# Connectors.net
KiCad netlist of a schematic drawn in Altium Designer
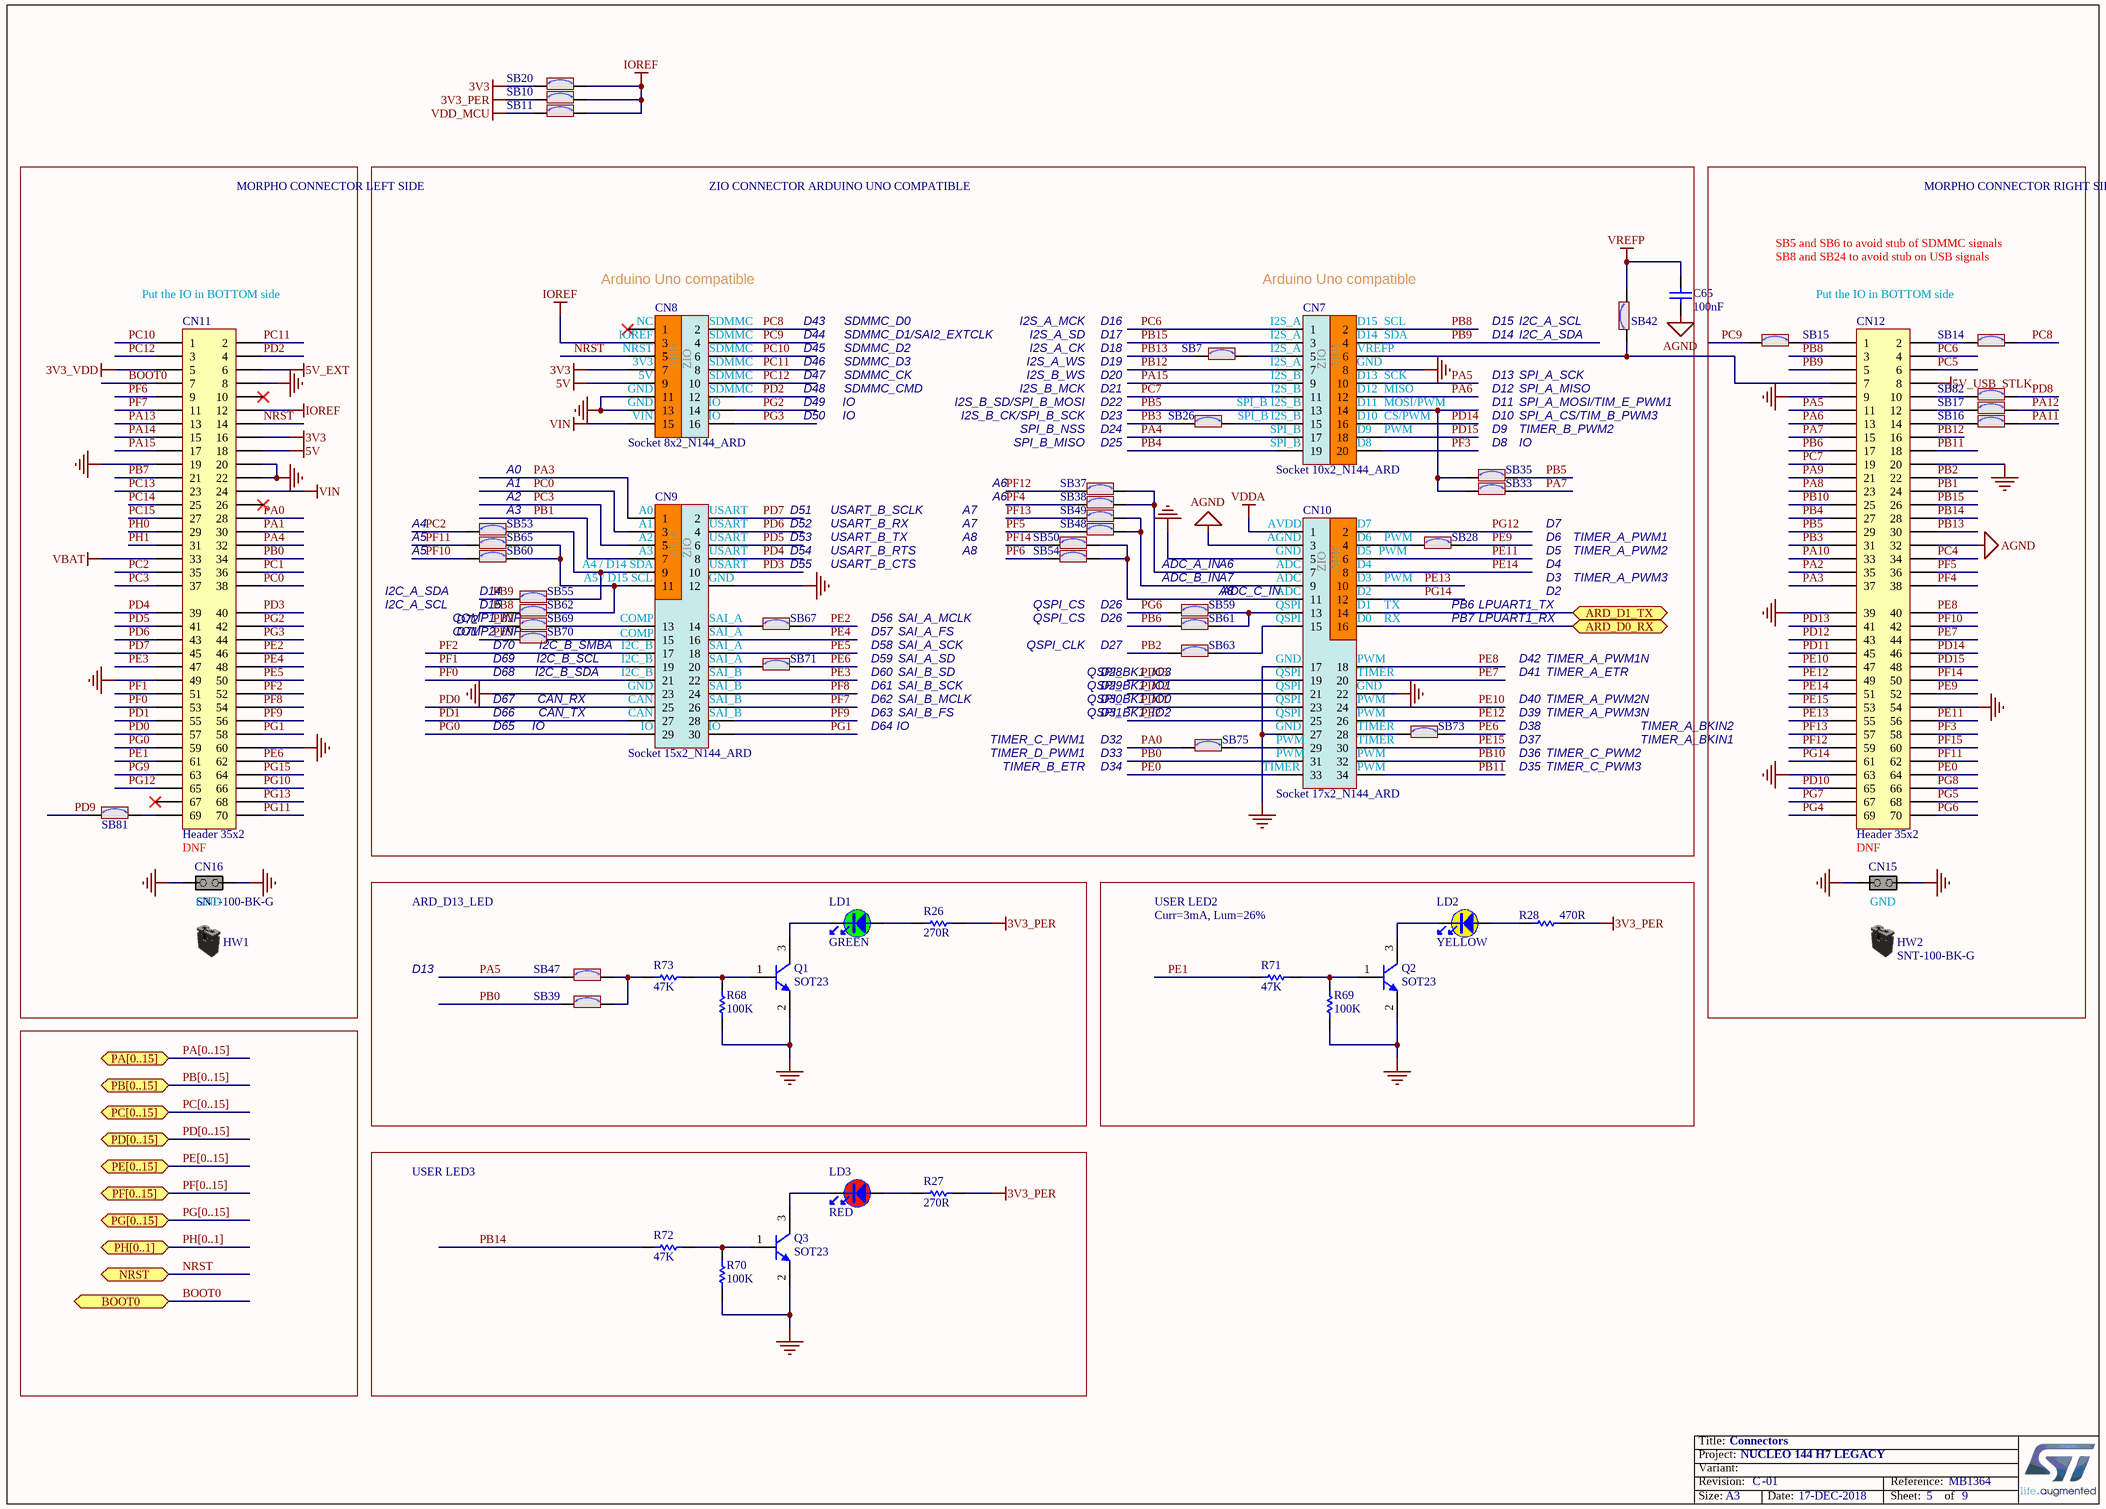
[diagram p0: Connectors.SchDoc]

(export (version "E")
  (design (tool "Eeschema 10.0.6"))
  (components
    (comp (ref "C65")
      (value "100nF")
      (footprint "C0603")
      (description "Capacitor, MLCC, 100nF, 6V3, X5R, 10%, 0603, T=0,8mm")
      (fields
        (field (name "INTERNAL_PART_NUMBER") "MCD-00237")
        (field (name "MANUFACTURER_PART_NUMBER") "CC0603KRX5R5BB104")
        (field (name "PROVIDED_BY") "SUBCO")
      )
      (libsource (lib "MCD_PARTS_database") (part "Capacitor"))
    )
    (comp (ref "CN7")
      (value "Socket 10x2_N144_ARD")
      (footprint "CON_SAMTEC_SSW-110-23-X-D_N144_ARD")
      (description "Socket, 10x2, 2.54mm, VR, TH, Height 8.51mm/10mm, Low insertion force.")
      (fields
        (field (name "INTERNAL_PART_NUMBER") "MCD-01039")
        (field (name "MANUFACTURER_PART_NUMBER") "SSW-110-23-x-D")
        (field (name "PROVIDED_BY") "SUBCO")
      )
      (libsource (lib "MCD_PARTS_database") (part "Socket 10x2_N144_ARD"))
    )
    (comp (ref "CN8")
      (value "Socket 8x2_N144_ARD")
      (footprint "CON_SAMTEC_SSW-108-23-X-D_N144_ARD")
      (description "Socket, 8x2, 2.54mm, VR, TH, Height 8.51mm/10mm, Low insertion force.")
      (fields
        (field (name "INTERNAL_PART_NUMBER") "MCD-01037")
        (field (name "MANUFACTURER_PART_NUMBER") "SSW-108-23-x-D")
        (field (name "PROVIDED_BY") "SUBCO")
      )
      (libsource (lib "MCD_PARTS_database") (part "Socket 8x2_N144_ARD"))
    )
    (comp (ref "CN9")
      (value "Socket 15x2_N144_ARD")
      (footprint "CON_SAMTEC_SSW-115-23-X-D_N144_ARD")
      (description "Socket, 15x2, 2.54mm, VR, TH, Height 8.51mm/10mm, Low insertion force.")
      (fields
        (field (name "INTERNAL_PART_NUMBER") "MCD-01040")
        (field (name "MANUFACTURER_PART_NUMBER") "SSW-115-23-x-D")
        (field (name "PROVIDED_BY") "SUBCO")
      )
      (libsource (lib "MCD_PARTS_database") (part "Socket 15x2_N144_ARD"))
    )
    (comp (ref "CN10")
      (value "Socket 17x2_N144_ARD")
      (footprint "CON_SAMTEC_SSW-117-23-X-D_N144_ARD")
      (description "Socket, 17x2, 2.54mm, VR, TH, Height 8.51mm/10mm, Low insertion force")
      (fields
        (field (name "INTERNAL_PART_NUMBER") "MCD-01041")
        (field (name "MANUFACTURER_PART_NUMBER") "SSW-117-23-x-D")
        (field (name "PROVIDED_BY") "SUBCO")
      )
      (libsource (lib "MCD_PARTS_database") (part "Socket 17x2_N144_ARD"))
    )
    (comp (ref "CN11")
      (value "Header 35x2")
      (footprint "CON_SAMTEC_TSW-135-07-X-D")
      (description "Header, 35x2, 2,54mm, VR, TH, Height 5.84mm/2.54mm")
      (fields
        (field (name "INTERNAL_PART_NUMBER") "MCD-01210")
        (field (name "MANUFACTURER_PART_NUMBER") "TSW-135-07-x-D")
        (field (name "PROVIDED_BY") "SUBCO")
      )
      (libsource (lib "MCD_PARTS_database") (part "Header 35x2"))
    )
    (comp (ref "CN12")
      (value "Header 35x2")
      (footprint "CON_SAMTEC_TSW-135-07-X-D")
      (description "Header, 35x2, 2,54mm, VR, TH, Height 5.84mm/2.54mm")
      (fields
        (field (name "INTERNAL_PART_NUMBER") "MCD-01210")
        (field (name "MANUFACTURER_PART_NUMBER") "TSW-135-07-x-D")
        (field (name "PROVIDED_BY") "SUBCO")
      )
      (libsource (lib "MCD_PARTS_database") (part "Header 35x2"))
    )
    (comp (ref "CN15")
      (value "Jumper_Header 2x1")
      (footprint "CON_SAMTEC_TSW-102-09-X-S")
      (description "Header, 2x1, 2,54mm, VR, TH, Height 5.84mm/10.16mm")
      (fields
        (field (name "INTERNAL_PART_NUMBER") "MCD-00214")
        (field (name "MANUFACTURER_PART_NUMBER") "TSW-102-09-x-S")
        (field (name "PROVIDED_BY") "SUBCO")
      )
      (libsource (lib "MCD_PARTS_database") (part "Jumper_Header 2x1"))
    )
    (comp (ref "CN16")
      (value "Jumper_Header 2x1")
      (footprint "CON_SAMTEC_TSW-102-09-X-S")
      (description "Header, 2x1, 2,54mm, VR, TH, Height 5.84mm/10.16mm")
      (fields
        (field (name "INTERNAL_PART_NUMBER") "MCD-00214")
        (field (name "MANUFACTURER_PART_NUMBER") "TSW-102-09-x-S")
        (field (name "PROVIDED_BY") "SUBCO")
      )
      (libsource (lib "MCD_PARTS_database") (part "Jumper_Header 2x1"))
    )
    (comp (ref "HW1")
      (value "SNT-100-BK-G")
      (description "SHUNT 2.54mm BLACK")
      (fields
        (field (name "INTERNAL_PART_NUMBER") "MCD-00043")
        (field (name "MANUFACTURER") "SAMTEC")
        (field (name "PROVIDED_BY") "SUBCO")
      )
      (libsource (lib "MCD_PARTS_database") (part "Shunt Black 2.54mm"))
    )
    (comp (ref "HW2")
      (value "SNT-100-BK-G")
      (description "SHUNT 2.54mm BLACK")
      (fields
        (field (name "INTERNAL_PART_NUMBER") "MCD-00043")
        (field (name "MANUFACTURER") "SAMTEC")
        (field (name "PROVIDED_BY") "SUBCO")
      )
      (libsource (lib "MCD_PARTS_database") (part "Shunt Black 2.54mm"))
    )
    (comp (ref "LD1")
      (value "GREEN")
      (footprint "LED_0603_OSRAM_LG-Q396-PS-35_GREEN_1A2K_H0P4")
      (description "LED Green, 0603 SMD, Forward Voltage Typ=2V, Max=2.5V")
      (fields
        (field (name "INTERNAL_PART_NUMBER") "MCD-00588")
        (field (name "MANUFACTURER_PART_NUMBER") "LG Q396-PS-35")
        (field (name "PROVIDED_BY") "SUBCO")
      )
      (libsource (lib "MCD_PARTS_database") (part "LED_green"))
    )
    (comp (ref "LD2")
      (value "YELLOW")
      (footprint "LED_0603_OSRAM_LY-Q396-P1Q2-36_YELLOW_1A2K_H0P4")
      (description "LED Yellow, 0603 SMD, Forward Voltage min=1.7V, Typ=2V, Max=2.3V")
      (fields
        (field (name "INTERNAL_PART_NUMBER") "MCD-01061")
        (field (name "MANUFACTURER_PART_NUMBER") "LY Q396-P1Q2-36")
        (field (name "PROVIDED_BY") "SUBCO")
      )
      (libsource (lib "MCD_PARTS_database") (part "LED_yellow"))
    )
    (comp (ref "LD3")
      (value "RED")
      (footprint "LED_0603_OSRAM_LS-Q976-NR-1_RED_1A2K_H0P8")
      (description "LED Red, 0603 SMD, Forward Voltage Typ=2V, Max=2.5V")
      (fields
        (field (name "INTERNAL_PART_NUMBER") "MCD-00586")
        (field (name "MANUFACTURER_PART_NUMBER") "LS Q976-NR-1")
        (field (name "PROVIDED_BY") "SUBCO")
      )
      (libsource (lib "MCD_PARTS_database") (part "LED_red"))
    )
    (comp (ref "Q1")
      (value "SOT23")
      (footprint "NPN_SOT23")
      (description "NPN Bipolar Transistor")
      (fields
        (field (name "INTERNAL_PART_NUMBER") "MCD-00073")
        (field (name "MANUFACTURER_PART_NUMBER") "BSR14")
        (field (name "PROVIDED_BY") "SUBCO")
      )
      (libsource (lib "MCD_PARTS_database") (part "9013-SOT23"))
    )
    (comp (ref "Q2")
      (value "SOT23")
      (footprint "NPN_SOT23")
      (description "NPN Bipolar Transistor")
      (fields
        (field (name "INTERNAL_PART_NUMBER") "MCD-00073")
        (field (name "MANUFACTURER_PART_NUMBER") "BSR14")
        (field (name "PROVIDED_BY") "SUBCO")
      )
      (libsource (lib "MCD_PARTS_database") (part "9013-SOT23"))
    )
    (comp (ref "Q3")
      (value "SOT23")
      (footprint "NPN_SOT23")
      (description "NPN Bipolar Transistor")
      (fields
        (field (name "INTERNAL_PART_NUMBER") "MCD-00073")
        (field (name "MANUFACTURER_PART_NUMBER") "BSR14")
        (field (name "PROVIDED_BY") "SUBCO")
      )
      (libsource (lib "MCD_PARTS_database") (part "9013-SOT23"))
    )
    (comp (ref "R26")
      (value "270R")
      (footprint "R0402")
      (description "Resistor,270R,0402,1%,1/16W")
      (fields
        (field (name "INTERNAL_PART_NUMBER") "MCD-00441")
        (field (name "MANUFACTURER_PART_NUMBER") "RC0402FR-07270RL")
        (field (name "PROVIDED_BY") "SUBCO")
      )
      (libsource (lib "MCD_PARTS_database") (part "Resistor"))
    )
    (comp (ref "R27")
      (value "270R")
      (footprint "R0402")
      (description "Resistor,270R,0402,1%,1/16W")
      (fields
        (field (name "INTERNAL_PART_NUMBER") "MCD-00441")
        (field (name "MANUFACTURER_PART_NUMBER") "RC0402FR-07270RL")
        (field (name "PROVIDED_BY") "SUBCO")
      )
      (libsource (lib "MCD_PARTS_database") (part "Resistor"))
    )
    (comp (ref "R28")
      (value "470R")
      (footprint "R0402")
      (description "Resistor,470R,0402,1%,1/16W")
      (fields
        (field (name "INTERNAL_PART_NUMBER") "MCD-00178")
        (field (name "MANUFACTURER_PART_NUMBER") "RC0402FR-07470RL")
        (field (name "PROVIDED_BY") "SUBCO")
      )
      (libsource (lib "MCD_PARTS_database") (part "Resistor"))
    )
    (comp (ref "R68")
      (value "100K")
      (footprint "R0603")
      (description "Resistor,100K,0603,1%,1/10W")
      (fields
        (field (name "INTERNAL_PART_NUMBER") "MCD-00223")
        (field (name "MANUFACTURER_PART_NUMBER") "RC0603FR-07100KL")
        (field (name "PROVIDED_BY") "SUBCO")
      )
      (libsource (lib "MCD_PARTS_database") (part "Resistor"))
    )
    (comp (ref "R69")
      (value "100K")
      (footprint "R0603")
      (description "Resistor,100K,0603,1%,1/10W")
      (fields
        (field (name "INTERNAL_PART_NUMBER") "MCD-00223")
        (field (name "MANUFACTURER_PART_NUMBER") "RC0603FR-07100KL")
        (field (name "PROVIDED_BY") "SUBCO")
      )
      (libsource (lib "MCD_PARTS_database") (part "Resistor"))
    )
    (comp (ref "R70")
      (value "100K")
      (footprint "R0603")
      (description "Resistor,100K,0603,1%,1/10W")
      (fields
        (field (name "INTERNAL_PART_NUMBER") "MCD-00223")
        (field (name "MANUFACTURER_PART_NUMBER") "RC0603FR-07100KL")
        (field (name "PROVIDED_BY") "SUBCO")
      )
      (libsource (lib "MCD_PARTS_database") (part "Resistor"))
    )
    (comp (ref "R71")
      (value "47K")
      (footprint "R0603")
      (description "Resistor,47K,0603,1%,1/10W")
      (fields
        (field (name "INTERNAL_PART_NUMBER") "MCD-00222")
        (field (name "MANUFACTURER_PART_NUMBER") "RC0603FR-0747KL")
        (field (name "PROVIDED_BY") "SUBCO")
      )
      (libsource (lib "MCD_PARTS_database") (part "Resistor"))
    )
    (comp (ref "R72")
      (value "47K")
      (footprint "R0603")
      (description "Resistor,47K,0603,1%,1/10W")
      (fields
        (field (name "INTERNAL_PART_NUMBER") "MCD-00222")
        (field (name "MANUFACTURER_PART_NUMBER") "RC0603FR-0747KL")
        (field (name "PROVIDED_BY") "SUBCO")
      )
      (libsource (lib "MCD_PARTS_database") (part "Resistor"))
    )
    (comp (ref "R73")
      (value "47K")
      (footprint "R0603")
      (description "Resistor,47K,0603,1%,1/10W")
      (fields
        (field (name "INTERNAL_PART_NUMBER") "MCD-00222")
        (field (name "MANUFACTURER_PART_NUMBER") "RC0603FR-0747KL")
        (field (name "PROVIDED_BY") "SUBCO")
      )
      (libsource (lib "MCD_PARTS_database") (part "Resistor"))
    )
    (comp (ref "SB7")
      (value "SB_ON")
      (footprint "SOLDER-BRIDGE_R0603-0R")
      (description "Solder Bridge ON")
      (fields
        (field (name "INTERNAL_PART_NUMBER") "MCD-00071")
        (field (name "MANUFACTURER_PART_NUMBER") "RC0603JR-070RL")
        (field (name "PROVIDED_BY") "SUBCO")
      )
      (libsource (lib "MCD_PARTS_database") (part "SB_ON"))
    )
    (comp (ref "SB10")
      (value "SB_ON")
      (footprint "SOLDER-BRIDGE_R0603-0R")
      (description "Solder Bridge ON")
      (fields
        (field (name "INTERNAL_PART_NUMBER") "MCD-00071")
        (field (name "MANUFACTURER_PART_NUMBER") "RC0603JR-070RL")
        (field (name "PROVIDED_BY") "SUBCO")
      )
      (libsource (lib "MCD_PARTS_database") (part "SB_ON"))
    )
    (comp (ref "SB11")
      (value "SB_ON")
      (footprint "SOLDER-BRIDGE_R0603-0R")
      (description "Solder Bridge ON")
      (fields
        (field (name "INTERNAL_PART_NUMBER") "MCD-00071")
        (field (name "MANUFACTURER_PART_NUMBER") "RC0603JR-070RL")
        (field (name "PROVIDED_BY") "SUBCO")
      )
      (libsource (lib "MCD_PARTS_database") (part "SB_ON"))
    )
    (comp (ref "SB14")
      (value "SB_ON")
      (footprint "SOLDER-BRIDGE_R0603-0R")
      (description "Solder Bridge ON")
      (fields
        (field (name "INTERNAL_PART_NUMBER") "MCD-00071")
        (field (name "MANUFACTURER_PART_NUMBER") "RC0603JR-070RL")
        (field (name "PROVIDED_BY") "SUBCO")
      )
      (libsource (lib "MCD_PARTS_database") (part "SB_ON"))
    )
    (comp (ref "SB15")
      (value "SB_ON")
      (footprint "SOLDER-BRIDGE_R0603-0R")
      (description "Solder Bridge ON")
      (fields
        (field (name "INTERNAL_PART_NUMBER") "MCD-00071")
        (field (name "MANUFACTURER_PART_NUMBER") "RC0603JR-070RL")
        (field (name "PROVIDED_BY") "SUBCO")
      )
      (libsource (lib "MCD_PARTS_database") (part "SB_ON"))
    )
    (comp (ref "SB16")
      (value "SB_ON")
      (footprint "SOLDER-BRIDGE_R0603-0R")
      (description "Solder Bridge ON")
      (fields
        (field (name "INTERNAL_PART_NUMBER") "MCD-00071")
        (field (name "MANUFACTURER_PART_NUMBER") "RC0603JR-070RL")
        (field (name "PROVIDED_BY") "SUBCO")
      )
      (libsource (lib "MCD_PARTS_database") (part "SB_ON"))
    )
    (comp (ref "SB17")
      (value "SB_ON")
      (footprint "SOLDER-BRIDGE_R0603-0R")
      (description "Solder Bridge ON")
      (fields
        (field (name "INTERNAL_PART_NUMBER") "MCD-00071")
        (field (name "MANUFACTURER_PART_NUMBER") "RC0603JR-070RL")
        (field (name "PROVIDED_BY") "SUBCO")
      )
      (libsource (lib "MCD_PARTS_database") (part "SB_ON"))
    )
    (comp (ref "SB20")
      (value "SB_ON")
      (footprint "SOLDER-BRIDGE_R0603-0R")
      (description "Solder Bridge ON")
      (fields
        (field (name "INTERNAL_PART_NUMBER") "MCD-00071")
        (field (name "MANUFACTURER_PART_NUMBER") "RC0603JR-070RL")
        (field (name "PROVIDED_BY") "SUBCO")
      )
      (libsource (lib "MCD_PARTS_database") (part "SB_ON"))
    )
    (comp (ref "SB26")
      (value "SB_ON")
      (footprint "SOLDER-BRIDGE_R0603-0R")
      (description "Solder Bridge ON")
      (fields
        (field (name "INTERNAL_PART_NUMBER") "MCD-00071")
        (field (name "MANUFACTURER_PART_NUMBER") "RC0603JR-070RL")
        (field (name "PROVIDED_BY") "SUBCO")
      )
      (libsource (lib "MCD_PARTS_database") (part "SB_ON"))
    )
    (comp (ref "SB28")
      (value "SB_ON")
      (footprint "SOLDER-BRIDGE_R0402-0R")
      (description "Solder Bridge 0402 ON")
      (fields
        (field (name "INTERNAL_PART_NUMBER") "MCD-01618")
        (field (name "MANUFACTURER_PART_NUMBER") "RC0402JR-070RL")
        (field (name "PROVIDED_BY") "SUBCO")
      )
      (libsource (lib "MCD_PARTS_database") (part "SB_ON"))
    )
    (comp (ref "SB33")
      (value "SB_ON")
      (footprint "SOLDER-BRIDGE_R0603-0R")
      (description "Solder Bridge ON")
      (fields
        (field (name "INTERNAL_PART_NUMBER") "MCD-00071")
        (field (name "MANUFACTURER_PART_NUMBER") "RC0603JR-070RL")
        (field (name "PROVIDED_BY") "SUBCO")
      )
      (libsource (lib "MCD_PARTS_database") (part "SB_ON"))
    )
    (comp (ref "SB35")
      (value "SB_ON")
      (footprint "SOLDER-BRIDGE_R0603-0R")
      (description "Solder Bridge ON")
      (fields
        (field (name "INTERNAL_PART_NUMBER") "MCD-00071")
        (field (name "MANUFACTURER_PART_NUMBER") "RC0603JR-070RL")
        (field (name "PROVIDED_BY") "SUBCO")
      )
      (libsource (lib "MCD_PARTS_database") (part "SB_ON"))
    )
    (comp (ref "SB37")
      (value "SB_ON")
      (footprint "SOLDER-BRIDGE_R0402-0R")
      (description "Solder Bridge 0402 ON")
      (fields
        (field (name "INTERNAL_PART_NUMBER") "MCD-01618")
        (field (name "MANUFACTURER_PART_NUMBER") "RC0402JR-070RL")
        (field (name "PROVIDED_BY") "SUBCO")
      )
      (libsource (lib "MCD_PARTS_database") (part "SB_ON"))
    )
    (comp (ref "SB38")
      (value "SB_ON")
      (footprint "SOLDER-BRIDGE_R0402-0R")
      (description "Solder Bridge 0402 ON")
      (fields
        (field (name "INTERNAL_PART_NUMBER") "MCD-01618")
        (field (name "MANUFACTURER_PART_NUMBER") "RC0402JR-070RL")
        (field (name "PROVIDED_BY") "SUBCO")
      )
      (libsource (lib "MCD_PARTS_database") (part "SB_ON"))
    )
    (comp (ref "SB39")
      (value "SB_ON")
      (footprint "SOLDER-BRIDGE_R0603-0R")
      (description "Solder Bridge ON")
      (fields
        (field (name "INTERNAL_PART_NUMBER") "MCD-00071")
        (field (name "MANUFACTURER_PART_NUMBER") "RC0603JR-070RL")
        (field (name "PROVIDED_BY") "SUBCO")
      )
      (libsource (lib "MCD_PARTS_database") (part "SB_ON"))
    )
    (comp (ref "SB42")
      (value "SB_ON")
      (footprint "SOLDER-BRIDGE_R0603-0R")
      (description "Solder Bridge ON")
      (fields
        (field (name "INTERNAL_PART_NUMBER") "MCD-00071")
        (field (name "MANUFACTURER_PART_NUMBER") "RC0603JR-070RL")
        (field (name "PROVIDED_BY") "SUBCO")
      )
      (libsource (lib "") (part "SB_ON_1"))
    )
    (comp (ref "SB47")
      (value "SB_ON")
      (footprint "SOLDER-BRIDGE_R0603-0R")
      (description "Solder Bridge ON")
      (fields
        (field (name "INTERNAL_PART_NUMBER") "MCD-00071")
        (field (name "MANUFACTURER_PART_NUMBER") "RC0603JR-070RL")
        (field (name "PROVIDED_BY") "SUBCO")
      )
      (libsource (lib "MCD_PARTS_database") (part "SB_ON"))
    )
    (comp (ref "SB48")
      (value "SB_ON")
      (footprint "SOLDER-BRIDGE_R0402-0R")
      (description "Solder Bridge 0402 ON")
      (fields
        (field (name "INTERNAL_PART_NUMBER") "MCD-01618")
        (field (name "MANUFACTURER_PART_NUMBER") "RC0402JR-070RL")
        (field (name "PROVIDED_BY") "SUBCO")
      )
      (libsource (lib "MCD_PARTS_database") (part "SB_ON"))
    )
    (comp (ref "SB49")
      (value "SB_ON")
      (footprint "SOLDER-BRIDGE_R0402-0R")
      (description "Solder Bridge 0402 ON")
      (fields
        (field (name "INTERNAL_PART_NUMBER") "MCD-01618")
        (field (name "MANUFACTURER_PART_NUMBER") "RC0402JR-070RL")
        (field (name "PROVIDED_BY") "SUBCO")
      )
      (libsource (lib "MCD_PARTS_database") (part "SB_ON"))
    )
    (comp (ref "SB50")
      (value "SB_ON")
      (footprint "SOLDER-BRIDGE_R0402-0R")
      (description "Solder Bridge 0402 ON")
      (fields
        (field (name "INTERNAL_PART_NUMBER") "MCD-01618")
        (field (name "MANUFACTURER_PART_NUMBER") "RC0402JR-070RL")
        (field (name "PROVIDED_BY") "SUBCO")
      )
      (libsource (lib "MCD_PARTS_database") (part "SB_ON"))
    )
    (comp (ref "SB53")
      (value "SB_ON")
      (footprint "SOLDER-BRIDGE_R0402-0R")
      (description "Solder Bridge 0402 ON")
      (fields
        (field (name "INTERNAL_PART_NUMBER") "MCD-01618")
        (field (name "MANUFACTURER_PART_NUMBER") "RC0402JR-070RL")
        (field (name "PROVIDED_BY") "SUBCO")
      )
      (libsource (lib "MCD_PARTS_database") (part "SB_ON"))
    )
    (comp (ref "SB54")
      (value "SB_ON")
      (footprint "SOLDER-BRIDGE_R0402-0R")
      (description "Solder Bridge 0402 ON")
      (fields
        (field (name "INTERNAL_PART_NUMBER") "MCD-01618")
        (field (name "MANUFACTURER_PART_NUMBER") "RC0402JR-070RL")
        (field (name "PROVIDED_BY") "SUBCO")
      )
      (libsource (lib "MCD_PARTS_database") (part "SB_ON"))
    )
    (comp (ref "SB55")
      (value "SB_ON")
      (footprint "SOLDER-BRIDGE_R0402-0R")
      (description "Solder Bridge 0402 ON")
      (fields
        (field (name "INTERNAL_PART_NUMBER") "MCD-01618")
        (field (name "MANUFACTURER_PART_NUMBER") "RC0402JR-070RL")
        (field (name "PROVIDED_BY") "SUBCO")
      )
      (libsource (lib "MCD_PARTS_database") (part "SB_ON"))
    )
    (comp (ref "SB59")
      (value "SB_ON")
      (footprint "SOLDER-BRIDGE_R0402-0R")
      (description "Solder Bridge 0402 ON")
      (fields
        (field (name "INTERNAL_PART_NUMBER") "MCD-01618")
        (field (name "MANUFACTURER_PART_NUMBER") "RC0402JR-070RL")
        (field (name "PROVIDED_BY") "SUBCO")
      )
      (libsource (lib "MCD_PARTS_database") (part "SB_ON"))
    )
    (comp (ref "SB60")
      (value "SB_ON")
      (footprint "SOLDER-BRIDGE_R0402-0R")
      (description "Solder Bridge 0402 ON")
      (fields
        (field (name "INTERNAL_PART_NUMBER") "MCD-01618")
        (field (name "MANUFACTURER_PART_NUMBER") "RC0402JR-070RL")
        (field (name "PROVIDED_BY") "SUBCO")
      )
      (libsource (lib "MCD_PARTS_database") (part "SB_ON"))
    )
    (comp (ref "SB61")
      (value "SB_ON")
      (footprint "SOLDER-BRIDGE_R0402-0R")
      (description "Solder Bridge 0402 ON")
      (fields
        (field (name "INTERNAL_PART_NUMBER") "MCD-01618")
        (field (name "MANUFACTURER_PART_NUMBER") "RC0402JR-070RL")
        (field (name "PROVIDED_BY") "SUBCO")
      )
      (libsource (lib "MCD_PARTS_database") (part "SB_ON"))
    )
    (comp (ref "SB62")
      (value "SB_ON")
      (footprint "SOLDER-BRIDGE_R0402-0R")
      (description "Solder Bridge 0402 ON")
      (fields
        (field (name "INTERNAL_PART_NUMBER") "MCD-01618")
        (field (name "MANUFACTURER_PART_NUMBER") "RC0402JR-070RL")
        (field (name "PROVIDED_BY") "SUBCO")
      )
      (libsource (lib "MCD_PARTS_database") (part "SB_ON"))
    )
    (comp (ref "SB63")
      (value "SB_ON")
      (footprint "SOLDER-BRIDGE_R0402-0R")
      (description "Solder Bridge 0402 ON")
      (fields
        (field (name "INTERNAL_PART_NUMBER") "MCD-01618")
        (field (name "MANUFACTURER_PART_NUMBER") "RC0402JR-070RL")
        (field (name "PROVIDED_BY") "SUBCO")
      )
      (libsource (lib "MCD_PARTS_database") (part "SB_ON"))
    )
    (comp (ref "SB65")
      (value "SB_ON")
      (footprint "SOLDER-BRIDGE_R0402-0R")
      (description "Solder Bridge 0402 ON")
      (fields
        (field (name "INTERNAL_PART_NUMBER") "MCD-01618")
        (field (name "MANUFACTURER_PART_NUMBER") "RC0402JR-070RL")
        (field (name "PROVIDED_BY") "SUBCO")
      )
      (libsource (lib "MCD_PARTS_database") (part "SB_ON"))
    )
    (comp (ref "SB67")
      (value "SB_ON")
      (footprint "SOLDER-BRIDGE_R0402-0R")
      (description "Solder Bridge 0402 ON")
      (fields
        (field (name "INTERNAL_PART_NUMBER") "MCD-01618")
        (field (name "MANUFACTURER_PART_NUMBER") "RC0402JR-070RL")
        (field (name "PROVIDED_BY") "SUBCO")
      )
      (libsource (lib "MCD_PARTS_database") (part "SB_ON"))
    )
    (comp (ref "SB69")
      (value "SB_ON")
      (footprint "SOLDER-BRIDGE_R0402-0R")
      (description "Solder Bridge 0402 ON")
      (fields
        (field (name "INTERNAL_PART_NUMBER") "MCD-01618")
        (field (name "MANUFACTURER_PART_NUMBER") "RC0402JR-070RL")
        (field (name "PROVIDED_BY") "SUBCO")
      )
      (libsource (lib "MCD_PARTS_database") (part "SB_ON"))
    )
    (comp (ref "SB70")
      (value "SB_ON")
      (footprint "SOLDER-BRIDGE_R0402-0R")
      (description "Solder Bridge 0402 ON")
      (fields
        (field (name "INTERNAL_PART_NUMBER") "MCD-01618")
        (field (name "MANUFACTURER_PART_NUMBER") "RC0402JR-070RL")
        (field (name "PROVIDED_BY") "SUBCO")
      )
      (libsource (lib "MCD_PARTS_database") (part "SB_ON"))
    )
    (comp (ref "SB71")
      (value "SB_ON")
      (footprint "SOLDER-BRIDGE_R0402-0R")
      (description "Solder Bridge 0402 ON")
      (fields
        (field (name "INTERNAL_PART_NUMBER") "MCD-01618")
        (field (name "MANUFACTURER_PART_NUMBER") "RC0402JR-070RL")
        (field (name "PROVIDED_BY") "SUBCO")
      )
      (libsource (lib "MCD_PARTS_database") (part "SB_ON"))
    )
    (comp (ref "SB73")
      (value "SB_ON")
      (footprint "SOLDER-BRIDGE_R0402-0R")
      (description "Solder Bridge 0402 ON")
      (fields
        (field (name "INTERNAL_PART_NUMBER") "MCD-01618")
        (field (name "MANUFACTURER_PART_NUMBER") "RC0402JR-070RL")
        (field (name "PROVIDED_BY") "SUBCO")
      )
      (libsource (lib "MCD_PARTS_database") (part "SB_ON"))
    )
    (comp (ref "SB75")
      (value "SB_ON")
      (footprint "SOLDER-BRIDGE_R0402-0R")
      (description "Solder Bridge 0402 ON")
      (fields
        (field (name "INTERNAL_PART_NUMBER") "MCD-01618")
        (field (name "MANUFACTURER_PART_NUMBER") "RC0402JR-070RL")
        (field (name "PROVIDED_BY") "SUBCO")
      )
      (libsource (lib "MCD_PARTS_database") (part "SB_ON"))
    )
    (comp (ref "SB81")
      (value "SB_ON")
      (footprint "SOLDER-BRIDGE_R0402-0R")
      (description "Solder Bridge 0402 ON")
      (fields
        (field (name "INTERNAL_PART_NUMBER") "MCD-01618")
        (field (name "MANUFACTURER_PART_NUMBER") "RC0402JR-070RL")
        (field (name "PROVIDED_BY") "SUBCO")
      )
      (libsource (lib "MCD_PARTS_database") (part "SB_ON"))
    )
    (comp (ref "SB82")
      (value "SB_ON")
      (footprint "SOLDER-BRIDGE_R0402-0R")
      (description "Solder Bridge 0402 ON")
      (fields
        (field (name "INTERNAL_PART_NUMBER") "MCD-01618")
        (field (name "MANUFACTURER_PART_NUMBER") "RC0402JR-070RL")
        (field (name "PROVIDED_BY") "SUBCO")
      )
      (libsource (lib "MCD_PARTS_database") (part "SB_ON"))
    )
  )
  (nets
    (net (code "1") (name "/ARD_D0_RX") (class "Default")
      (node (ref "CN10") (pin "16") (pinfunction "16_16") (pintype "passive"))
    )
    (net (code "2") (name "/ARD_D1_TX") (class "Default")
      (node (ref "CN10") (pin "14") (pinfunction "14_14") (pintype "passive"))
    )
    (net (code "3") (name "/BOOT0") (class "Default")
      (node (ref "CN11") (pin "7") (pinfunction "7_7") (pintype "passive"))
    )
    (net (code "4") (name "/NRST") (class "Default")
      (node (ref "CN11") (pin "14") (pinfunction "14_14") (pintype "passive"))
      (node (ref "CN8") (pin "5") (pinfunction "5_5") (pintype "passive"))
    )
    (net (code "5") (name "/PA0") (class "Default")
      (node (ref "CN11") (pin "28") (pinfunction "28_28") (pintype "passive"))
      (node (ref "SB75") (pin "1") (pinfunction "1_1") (pintype "passive"))
    )
    (net (code "6") (name "/PA1") (class "Default")
      (node (ref "CN11") (pin "30") (pinfunction "30_30") (pintype "passive"))
    )
    (net (code "7") (name "/PA2") (class "Default")
      (node (ref "CN12") (pin "35") (pinfunction "35_35") (pintype "passive"))
    )
    (net (code "8") (name "/PA3") (class "Default")
      (node (ref "CN12") (pin "37") (pinfunction "37_37") (pintype "passive"))
      (node (ref "CN9") (pin "1") (pinfunction "1_1") (pintype "passive"))
    )
    (net (code "9") (name "/PA4") (class "Default")
      (node (ref "CN11") (pin "32") (pinfunction "32_32") (pintype "passive"))
      (node (ref "CN7") (pin "17") (pinfunction "17_17") (pintype "passive"))
    )
    (net (code "10") (name "/PA5") (class "Default")
      (node (ref "CN12") (pin "11") (pinfunction "11_11") (pintype "passive"))
      (node (ref "CN7") (pin "10") (pinfunction "10_10") (pintype "passive"))
      (node (ref "SB47") (pin "1") (pinfunction "1_1") (pintype "passive"))
    )
    (net (code "11") (name "/PA6") (class "Default")
      (node (ref "CN12") (pin "13") (pinfunction "13_13") (pintype "passive"))
      (node (ref "CN7") (pin "12") (pinfunction "12_12") (pintype "passive"))
    )
    (net (code "12") (name "/PA7") (class "Default")
      (node (ref "CN12") (pin "15") (pinfunction "15_15") (pintype "passive"))
      (node (ref "SB33") (pin "2") (pinfunction "2_2") (pintype "passive"))
    )
    (net (code "13") (name "/PA8") (class "Default")
      (node (ref "CN12") (pin "23") (pinfunction "23_23") (pintype "passive"))
    )
    (net (code "14") (name "/PA9") (class "Default")
      (node (ref "CN12") (pin "21") (pinfunction "21_21") (pintype "passive"))
    )
    (net (code "15") (name "/PA10") (class "Default")
      (node (ref "CN12") (pin "33") (pinfunction "33_33") (pintype "passive"))
    )
    (net (code "16") (name "/PA11") (class "Default")
      (node (ref "SB16") (pin "2") (pinfunction "2_2") (pintype "passive"))
    )
    (net (code "17") (name "/PA12") (class "Default")
      (node (ref "SB17") (pin "2") (pinfunction "2_2") (pintype "passive"))
    )
    (net (code "18") (name "/PA13") (class "Default")
      (node (ref "CN11") (pin "13") (pinfunction "13_13") (pintype "passive"))
    )
    (net (code "19") (name "/PA14") (class "Default")
      (node (ref "CN11") (pin "15") (pinfunction "15_15") (pintype "passive"))
    )
    (net (code "20") (name "/PA15") (class "Default")
      (node (ref "CN11") (pin "17") (pinfunction "17_17") (pintype "passive"))
      (node (ref "CN7") (pin "9") (pinfunction "9_9") (pintype "passive"))
    )
    (net (code "22") (name "/PB0") (class "Default")
      (node (ref "CN10") (pin "31") (pinfunction "31_31") (pintype "passive"))
      (node (ref "CN11") (pin "34") (pinfunction "34_34") (pintype "passive"))
      (node (ref "SB39") (pin "1") (pinfunction "1_1") (pintype "passive"))
    )
    (net (code "23") (name "/PB1") (class "Default")
      (node (ref "CN12") (pin "24") (pinfunction "24_24") (pintype "passive"))
      (node (ref "CN9") (pin "7") (pinfunction "7_7") (pintype "passive"))
    )
    (net (code "24") (name "/PB2") (class "Default")
      (node (ref "CN12") (pin "22") (pinfunction "22_22") (pintype "passive"))
      (node (ref "SB63") (pin "1") (pinfunction "1_1") (pintype "passive"))
      (node (ref "SB69") (pin "1") (pinfunction "1_1") (pintype "passive"))
    )
    (net (code "25") (name "/PB3") (class "Default")
      (node (ref "CN12") (pin "31") (pinfunction "31_31") (pintype "passive"))
      (node (ref "SB26") (pin "1") (pinfunction "1_1") (pintype "passive"))
    )
    (net (code "26") (name "/PB4") (class "Default")
      (node (ref "CN12") (pin "27") (pinfunction "27_27") (pintype "passive"))
      (node (ref "CN7") (pin "19") (pinfunction "19_19") (pintype "passive"))
    )
    (net (code "27") (name "/PB5") (class "Default")
      (node (ref "CN12") (pin "29") (pinfunction "29_29") (pintype "passive"))
      (node (ref "CN7") (pin "13") (pinfunction "13_13") (pintype "passive"))
      (node (ref "SB35") (pin "2") (pinfunction "2_2") (pintype "passive"))
    )
    (net (code "28") (name "/PB6") (class "Default")
      (node (ref "CN12") (pin "17") (pinfunction "17_17") (pintype "passive"))
      (node (ref "SB61") (pin "1") (pinfunction "1_1") (pintype "passive"))
    )
    (net (code "29") (name "/PB7") (class "Default")
      (node (ref "CN11") (pin "21") (pinfunction "21_21") (pintype "passive"))
    )
    (net (code "30") (name "/PB8") (class "Default")
      (node (ref "CN12") (pin "3") (pinfunction "3_3") (pintype "passive"))
      (node (ref "CN7") (pin "2") (pinfunction "2_2") (pintype "passive"))
      (node (ref "SB62") (pin "1") (pinfunction "1_1") (pintype "passive"))
    )
    (net (code "31") (name "/PB9") (class "Default")
      (node (ref "CN12") (pin "5") (pinfunction "5_5") (pintype "passive"))
      (node (ref "CN7") (pin "4") (pinfunction "4_4") (pintype "passive"))
      (node (ref "SB55") (pin "1") (pinfunction "1_1") (pintype "passive"))
    )
    (net (code "32") (name "/PB10") (class "Default")
      (node (ref "CN10") (pin "32") (pinfunction "32_32") (pintype "passive"))
      (node (ref "CN12") (pin "25") (pinfunction "25_25") (pintype "passive"))
    )
    (net (code "33") (name "/PB11") (class "Default")
      (node (ref "CN10") (pin "34") (pinfunction "34_34") (pintype "passive"))
      (node (ref "CN12") (pin "18") (pinfunction "18_18") (pintype "passive"))
    )
    (net (code "34") (name "/PB12") (class "Default")
      (node (ref "CN12") (pin "16") (pinfunction "16_16") (pintype "passive"))
      (node (ref "CN7") (pin "7") (pinfunction "7_7") (pintype "passive"))
    )
    (net (code "35") (name "/PB13") (class "Default")
      (node (ref "CN12") (pin "30") (pinfunction "30_30") (pintype "passive"))
      (node (ref "SB7") (pin "1") (pinfunction "1_1") (pintype "passive"))
    )
    (net (code "36") (name "/PB14") (class "Default")
      (node (ref "CN12") (pin "28") (pinfunction "28_28") (pintype "passive"))
      (node (ref "R72") (pin "1") (pinfunction "1_1") (pintype "passive"))
    )
    (net (code "37") (name "/PB15") (class "Default")
      (node (ref "CN12") (pin "26") (pinfunction "26_26") (pintype "passive"))
      (node (ref "CN7") (pin "3") (pinfunction "3_3") (pintype "passive"))
    )
    (net (code "39") (name "/PC0") (class "Default")
      (node (ref "CN11") (pin "38") (pinfunction "38_38") (pintype "passive"))
      (node (ref "CN9") (pin "3") (pinfunction "3_3") (pintype "passive"))
    )
    (net (code "40") (name "/PC1") (class "Default")
      (node (ref "CN11") (pin "36") (pinfunction "36_36") (pintype "passive"))
    )
    (net (code "41") (name "/PC2") (class "Default")
      (node (ref "CN11") (pin "35") (pinfunction "35_35") (pintype "passive"))
      (node (ref "SB53") (pin "1") (pinfunction "1_1") (pintype "passive"))
    )
    (net (code "42") (name "/PC3") (class "Default")
      (node (ref "CN11") (pin "37") (pinfunction "37_37") (pintype "passive"))
      (node (ref "CN9") (pin "5") (pinfunction "5_5") (pintype "passive"))
    )
    (net (code "43") (name "/PC4") (class "Default")
      (node (ref "CN12") (pin "34") (pinfunction "34_34") (pintype "passive"))
    )
    (net (code "44") (name "/PC5") (class "Default")
      (node (ref "CN12") (pin "6") (pinfunction "6_6") (pintype "passive"))
    )
    (net (code "45") (name "/PC6") (class "Default")
      (node (ref "CN12") (pin "4") (pinfunction "4_4") (pintype "passive"))
      (node (ref "CN7") (pin "1") (pinfunction "1_1") (pintype "passive"))
    )
    (net (code "46") (name "/PC7") (class "Default")
      (node (ref "CN12") (pin "19") (pinfunction "19_19") (pintype "passive"))
      (node (ref "CN7") (pin "11") (pinfunction "11_11") (pintype "passive"))
    )
    (net (code "47") (name "/PC8") (class "Default")
      (node (ref "CN8") (pin "2") (pinfunction "2_2") (pintype "passive"))
      (node (ref "SB14") (pin "2") (pinfunction "2_2") (pintype "passive"))
    )
    (net (code "48") (name "/PC9") (class "Default")
      (node (ref "CN8") (pin "4") (pinfunction "4_4") (pintype "passive"))
      (node (ref "SB15") (pin "1") (pinfunction "1_1") (pintype "passive"))
    )
    (net (code "49") (name "/PC10") (class "Default")
      (node (ref "CN11") (pin "1") (pinfunction "1_1") (pintype "passive"))
      (node (ref "CN8") (pin "6") (pinfunction "6_6") (pintype "passive"))
    )
    (net (code "50") (name "/PC11") (class "Default")
      (node (ref "CN11") (pin "2") (pinfunction "2_2") (pintype "passive"))
      (node (ref "CN8") (pin "8") (pinfunction "8_8") (pintype "passive"))
    )
    (net (code "51") (name "/PC12") (class "Default")
      (node (ref "CN11") (pin "3") (pinfunction "3_3") (pintype "passive"))
      (node (ref "CN8") (pin "10") (pinfunction "10_10") (pintype "passive"))
    )
    (net (code "52") (name "/PC13") (class "Default")
      (node (ref "CN11") (pin "23") (pinfunction "23_23") (pintype "passive"))
    )
    (net (code "53") (name "/PC14") (class "Default")
      (node (ref "CN11") (pin "25") (pinfunction "25_25") (pintype "passive"))
    )
    (net (code "54") (name "/PC15") (class "Default")
      (node (ref "CN11") (pin "27") (pinfunction "27_27") (pintype "passive"))
    )
    (net (code "56") (name "/PD0") (class "Default")
      (node (ref "CN11") (pin "57") (pinfunction "57_57") (pintype "passive"))
      (node (ref "CN9") (pin "25") (pinfunction "25_25") (pintype "passive"))
    )
    (net (code "57") (name "/PD1") (class "Default")
      (node (ref "CN11") (pin "55") (pinfunction "55_55") (pintype "passive"))
      (node (ref "CN9") (pin "27") (pinfunction "27_27") (pintype "passive"))
    )
    (net (code "58") (name "/PD2") (class "Default")
      (node (ref "CN11") (pin "4") (pinfunction "4_4") (pintype "passive"))
      (node (ref "CN8") (pin "12") (pinfunction "12_12") (pintype "passive"))
    )
    (net (code "59") (name "/PD3") (class "Default")
      (node (ref "CN11") (pin "40") (pinfunction "40_40") (pintype "passive"))
      (node (ref "CN9") (pin "10") (pinfunction "10_10") (pintype "passive"))
    )
    (net (code "60") (name "/PD4") (class "Default")
      (node (ref "CN11") (pin "39") (pinfunction "39_39") (pintype "passive"))
      (node (ref "CN9") (pin "8") (pinfunction "8_8") (pintype "passive"))
    )
    (net (code "61") (name "/PD5") (class "Default")
      (node (ref "CN11") (pin "41") (pinfunction "41_41") (pintype "passive"))
      (node (ref "CN9") (pin "6") (pinfunction "6_6") (pintype "passive"))
    )
    (net (code "62") (name "/PD6") (class "Default")
      (node (ref "CN11") (pin "43") (pinfunction "43_43") (pintype "passive"))
      (node (ref "CN9") (pin "4") (pinfunction "4_4") (pintype "passive"))
    )
    (net (code "63") (name "/PD7") (class "Default")
      (node (ref "CN11") (pin "45") (pinfunction "45_45") (pintype "passive"))
      (node (ref "CN9") (pin "2") (pinfunction "2_2") (pintype "passive"))
    )
    (net (code "64") (name "/PD8") (class "Default")
      (node (ref "SB82") (pin "2") (pinfunction "2_2") (pintype "passive"))
    )
    (net (code "65") (name "/PD9") (class "Default")
      (node (ref "SB81") (pin "1") (pinfunction "1_1") (pintype "passive"))
    )
    (net (code "66") (name "/PD10") (class "Default")
      (node (ref "CN12") (pin "65") (pinfunction "65_65") (pintype "passive"))
    )
    (net (code "67") (name "/PD11") (class "Default")
      (node (ref "CN10") (pin "23") (pinfunction "23_23") (pintype "passive"))
      (node (ref "CN12") (pin "45") (pinfunction "45_45") (pintype "passive"))
    )
    (net (code "68") (name "/PD12") (class "Default")
      (node (ref "CN10") (pin "21") (pinfunction "21_21") (pintype "passive"))
      (node (ref "CN12") (pin "43") (pinfunction "43_43") (pintype "passive"))
    )
    (net (code "69") (name "/PD13") (class "Default")
      (node (ref "CN10") (pin "19") (pinfunction "19_19") (pintype "passive"))
      (node (ref "CN12") (pin "41") (pinfunction "41_41") (pintype "passive"))
    )
    (net (code "70") (name "/PD14") (class "Default")
      (node (ref "CN12") (pin "46") (pinfunction "46_46") (pintype "passive"))
      (node (ref "CN7") (pin "16") (pinfunction "16_16") (pintype "passive"))
    )
    (net (code "71") (name "/PD15") (class "Default")
      (node (ref "CN12") (pin "48") (pinfunction "48_48") (pintype "passive"))
      (node (ref "CN7") (pin "18") (pinfunction "18_18") (pintype "passive"))
    )
    (net (code "73") (name "/PE0") (class "Default")
      (node (ref "CN10") (pin "33") (pinfunction "33_33") (pintype "passive"))
      (node (ref "CN12") (pin "64") (pinfunction "64_64") (pintype "passive"))
    )
    (net (code "74") (name "/PE1") (class "Default")
      (node (ref "CN11") (pin "61") (pinfunction "61_61") (pintype "passive"))
      (node (ref "R71") (pin "1") (pinfunction "1_1") (pintype "passive"))
    )
    (net (code "75") (name "/PE2") (class "Default")
      (node (ref "CN10") (pin "25") (pinfunction "25_25") (pintype "passive"))
      (node (ref "CN11") (pin "46") (pinfunction "46_46") (pintype "passive"))
      (node (ref "SB67") (pin "2") (pinfunction "2_2") (pintype "passive"))
    )
    (net (code "76") (name "/PE3") (class "Default")
      (node (ref "CN11") (pin "47") (pinfunction "47_47") (pintype "passive"))
      (node (ref "CN9") (pin "22") (pinfunction "22_22") (pintype "passive"))
    )
    (net (code "77") (name "/PE4") (class "Default")
      (node (ref "CN11") (pin "48") (pinfunction "48_48") (pintype "passive"))
      (node (ref "CN9") (pin "16") (pinfunction "16_16") (pintype "passive"))
    )
    (net (code "78") (name "/PE5") (class "Default")
      (node (ref "CN11") (pin "50") (pinfunction "50_50") (pintype "passive"))
      (node (ref "CN9") (pin "18") (pinfunction "18_18") (pintype "passive"))
    )
    (net (code "79") (name "/PE6") (class "Default")
      (node (ref "CN11") (pin "62") (pinfunction "62_62") (pintype "passive"))
      (node (ref "SB71") (pin "2") (pinfunction "2_2") (pintype "passive"))
      (node (ref "SB73") (pin "2") (pinfunction "2_2") (pintype "passive"))
    )
    (net (code "80") (name "/PE7") (class "Default")
      (node (ref "CN10") (pin "20") (pinfunction "20_20") (pintype "passive"))
      (node (ref "CN12") (pin "44") (pinfunction "44_44") (pintype "passive"))
    )
    (net (code "81") (name "/PE8") (class "Default")
      (node (ref "CN10") (pin "18") (pinfunction "18_18") (pintype "passive"))
      (node (ref "CN12") (pin "40") (pinfunction "40_40") (pintype "passive"))
    )
    (net (code "82") (name "/PE9") (class "Default")
      (node (ref "CN12") (pin "52") (pinfunction "52_52") (pintype "passive"))
      (node (ref "SB28") (pin "2") (pinfunction "2_2") (pintype "passive"))
      (node (ref "SB70") (pin "1") (pinfunction "1_1") (pintype "passive"))
    )
    (net (code "83") (name "/PE10") (class "Default")
      (node (ref "CN10") (pin "24") (pinfunction "24_24") (pintype "passive"))
      (node (ref "CN12") (pin "47") (pinfunction "47_47") (pintype "passive"))
    )
    (net (code "84") (name "/PE11") (class "Default")
      (node (ref "CN10") (pin "6") (pinfunction "6_6") (pintype "passive"))
      (node (ref "CN12") (pin "56") (pinfunction "56_56") (pintype "passive"))
    )
    (net (code "85") (name "/PE12") (class "Default")
      (node (ref "CN10") (pin "26") (pinfunction "26_26") (pintype "passive"))
      (node (ref "CN12") (pin "49") (pinfunction "49_49") (pintype "passive"))
    )
    (net (code "86") (name "/PE13") (class "Default")
      (node (ref "CN10") (pin "10") (pinfunction "10_10") (pintype "passive"))
      (node (ref "CN12") (pin "55") (pinfunction "55_55") (pintype "passive"))
    )
    (net (code "87") (name "/PE14") (class "Default")
      (node (ref "CN10") (pin "8") (pinfunction "8_8") (pintype "passive"))
      (node (ref "CN12") (pin "51") (pinfunction "51_51") (pintype "passive"))
    )
    (net (code "88") (name "/PE15") (class "Default")
      (node (ref "CN10") (pin "30") (pinfunction "30_30") (pintype "passive"))
      (node (ref "CN12") (pin "53") (pinfunction "53_53") (pintype "passive"))
    )
    (net (code "90") (name "/PF0") (class "Default")
      (node (ref "CN11") (pin "53") (pinfunction "53_53") (pintype "passive"))
      (node (ref "CN9") (pin "21") (pinfunction "21_21") (pintype "passive"))
    )
    (net (code "91") (name "/PF1") (class "Default")
      (node (ref "CN11") (pin "51") (pinfunction "51_51") (pintype "passive"))
      (node (ref "CN9") (pin "19") (pinfunction "19_19") (pintype "passive"))
    )
    (net (code "92") (name "/PF2") (class "Default")
      (node (ref "CN11") (pin "52") (pinfunction "52_52") (pintype "passive"))
      (node (ref "CN9") (pin "17") (pinfunction "17_17") (pintype "passive"))
    )
    (net (code "93") (name "/PF3") (class "Default")
      (node (ref "CN12") (pin "58") (pinfunction "58_58") (pintype "passive"))
      (node (ref "CN7") (pin "20") (pinfunction "20_20") (pintype "passive"))
    )
    (net (code "94") (name "/PF4") (class "Default")
      (node (ref "CN12") (pin "38") (pinfunction "38_38") (pintype "passive"))
      (node (ref "SB38") (pin "1") (pinfunction "1_1") (pintype "passive"))
    )
    (net (code "95") (name "/PF5") (class "Default")
      (node (ref "CN12") (pin "36") (pinfunction "36_36") (pintype "passive"))
      (node (ref "SB48") (pin "1") (pinfunction "1_1") (pintype "passive"))
    )
    (net (code "96") (name "/PF6") (class "Default")
      (node (ref "CN11") (pin "9") (pinfunction "9_9") (pintype "passive"))
      (node (ref "SB54") (pin "1") (pinfunction "1_1") (pintype "passive"))
    )
    (net (code "97") (name "/PF7") (class "Default")
      (node (ref "CN11") (pin "11") (pinfunction "11_11") (pintype "passive"))
      (node (ref "CN9") (pin "26") (pinfunction "26_26") (pintype "passive"))
    )
    (net (code "98") (name "/PF8") (class "Default")
      (node (ref "CN11") (pin "54") (pinfunction "54_54") (pintype "passive"))
      (node (ref "CN9") (pin "24") (pinfunction "24_24") (pintype "passive"))
    )
    (net (code "99") (name "/PF9") (class "Default")
      (node (ref "CN11") (pin "56") (pinfunction "56_56") (pintype "passive"))
      (node (ref "CN9") (pin "28") (pinfunction "28_28") (pintype "passive"))
    )
    (net (code "100") (name "/PF10") (class "Default")
      (node (ref "CN12") (pin "42") (pinfunction "42_42") (pintype "passive"))
      (node (ref "SB60") (pin "1") (pinfunction "1_1") (pintype "passive"))
    )
    (net (code "101") (name "/PF11") (class "Default")
      (node (ref "CN12") (pin "62") (pinfunction "62_62") (pintype "passive"))
      (node (ref "SB65") (pin "1") (pinfunction "1_1") (pintype "passive"))
    )
    (net (code "102") (name "/PF12") (class "Default")
      (node (ref "CN12") (pin "59") (pinfunction "59_59") (pintype "passive"))
      (node (ref "SB37") (pin "1") (pinfunction "1_1") (pintype "passive"))
    )
    (net (code "103") (name "/PF13") (class "Default")
      (node (ref "CN12") (pin "57") (pinfunction "57_57") (pintype "passive"))
      (node (ref "SB49") (pin "1") (pinfunction "1_1") (pintype "passive"))
    )
    (net (code "104") (name "/PF14") (class "Default")
      (node (ref "CN12") (pin "50") (pinfunction "50_50") (pintype "passive"))
      (node (ref "SB50") (pin "1") (pinfunction "1_1") (pintype "passive"))
    )
    (net (code "105") (name "/PF15") (class "Default")
      (node (ref "CN12") (pin "60") (pinfunction "60_60") (pintype "passive"))
    )
    (net (code "107") (name "/PG0") (class "Default")
      (node (ref "CN11") (pin "59") (pinfunction "59_59") (pintype "passive"))
      (node (ref "CN9") (pin "29") (pinfunction "29_29") (pintype "passive"))
    )
    (net (code "108") (name "/PG1") (class "Default")
      (node (ref "CN11") (pin "58") (pinfunction "58_58") (pintype "passive"))
      (node (ref "CN9") (pin "30") (pinfunction "30_30") (pintype "passive"))
    )
    (net (code "109") (name "/PG2") (class "Default")
      (node (ref "CN11") (pin "42") (pinfunction "42_42") (pintype "passive"))
      (node (ref "CN8") (pin "14") (pinfunction "14_14") (pintype "passive"))
    )
    (net (code "110") (name "/PG3") (class "Default")
      (node (ref "CN11") (pin "44") (pinfunction "44_44") (pintype "passive"))
      (node (ref "CN8") (pin "16") (pinfunction "16_16") (pintype "passive"))
    )
    (net (code "111") (name "/PG4") (class "Default")
      (node (ref "CN12") (pin "69") (pinfunction "69_69") (pintype "passive"))
    )
    (net (code "112") (name "/PG5") (class "Default")
      (node (ref "CN12") (pin "68") (pinfunction "68_68") (pintype "passive"))
    )
    (net (code "113") (name "/PG6") (class "Default")
      (node (ref "CN12") (pin "70") (pinfunction "70_70") (pintype "passive"))
      (node (ref "SB59") (pin "1") (pinfunction "1_1") (pintype "passive"))
    )
    (net (code "114") (name "/PG7") (class "Default")
      (node (ref "CN12") (pin "67") (pinfunction "67_67") (pintype "passive"))
    )
    (net (code "115") (name "/PG8") (class "Default")
      (node (ref "CN12") (pin "66") (pinfunction "66_66") (pintype "passive"))
    )
    (net (code "116") (name "/PG9") (class "Default")
      (node (ref "CN11") (pin "63") (pinfunction "63_63") (pintype "passive"))
    )
    (net (code "117") (name "/PG10") (class "Default")
      (node (ref "CN11") (pin "66") (pinfunction "66_66") (pintype "passive"))
    )
    (net (code "118") (name "/PG11") (class "Default")
      (node (ref "CN11") (pin "70") (pinfunction "70_70") (pintype "passive"))
    )
    (net (code "119") (name "/PG12") (class "Default")
      (node (ref "CN10") (pin "2") (pinfunction "2_2") (pintype "passive"))
      (node (ref "CN11") (pin "65") (pinfunction "65_65") (pintype "passive"))
    )
    (net (code "120") (name "/PG13") (class "Default")
      (node (ref "CN11") (pin "68") (pinfunction "68_68") (pintype "passive"))
    )
    (net (code "121") (name "/PG14") (class "Default")
      (node (ref "CN10") (pin "12") (pinfunction "12_12") (pintype "passive"))
      (node (ref "CN12") (pin "61") (pinfunction "61_61") (pintype "passive"))
    )
    (net (code "122") (name "/PG15") (class "Default")
      (node (ref "CN11") (pin "64") (pinfunction "64_64") (pintype "passive"))
    )
    (net (code "124") (name "/PH0") (class "Default")
      (node (ref "CN11") (pin "29") (pinfunction "29_29") (pintype "passive"))
    )
    (net (code "125") (name "/PH1") (class "Default")
      (node (ref "CN11") (pin "31") (pinfunction "31_31") (pintype "passive"))
    )
    (net (code "127") (name "3V3") (class "Default")
      (node (ref "CN11") (pin "16") (pinfunction "16_16") (pintype "passive"))
      (node (ref "CN8") (pin "7") (pinfunction "7_7") (pintype "passive"))
      (node (ref "SB20") (pin "1") (pinfunction "1_1") (pintype "passive"))
    )
    (net (code "128") (name "3V3_PER") (class "Default")
      (node (ref "R26") (pin "2") (pinfunction "2_2") (pintype "passive"))
      (node (ref "R27") (pin "2") (pinfunction "2_2") (pintype "passive"))
      (node (ref "R28") (pin "2") (pinfunction "2_2") (pintype "passive"))
      (node (ref "SB10") (pin "1") (pinfunction "1_1") (pintype "passive"))
    )
    (net (code "129") (name "3V3_VDD") (class "Default")
      (node (ref "CN11") (pin "5") (pinfunction "5_5") (pintype "passive"))
    )
    (net (code "130") (name "5V") (class "Default")
      (node (ref "CN11") (pin "18") (pinfunction "18_18") (pintype "passive"))
      (node (ref "CN8") (pin "9") (pinfunction "9_9") (pintype "passive"))
    )
    (net (code "131") (name "5V_EXT") (class "Default")
      (node (ref "CN11") (pin "6") (pinfunction "6_6") (pintype "passive"))
    )
    (net (code "132") (name "5V_USB_STLK") (class "Default")
      (node (ref "CN12") (pin "8") (pinfunction "8_8") (pintype "passive"))
    )
    (net (code "133") (name "AGND") (class "Default")
      (node (ref "C65") (pin "1") (pinfunction "1_1") (pintype "passive"))
      (node (ref "CN10") (pin "3") (pinfunction "3_3") (pintype "passive"))
      (node (ref "CN12") (pin "32") (pinfunction "32_32") (pintype "passive"))
    )
    (net (code "134") (name "GND") (class "Default")
      (node (ref "CN10") (pin "17") (pinfunction "17_17") (pintype "passive"))
      (node (ref "CN10") (pin "22") (pinfunction "22_22") (pintype "passive"))
      (node (ref "CN10") (pin "27") (pinfunction "27_27") (pintype "passive"))
      (node (ref "CN10") (pin "5") (pinfunction "5_5") (pintype "passive"))
      (node (ref "CN11") (pin "19") (pinfunction "19_19") (pintype "passive"))
      (node (ref "CN11") (pin "20") (pinfunction "20_20") (pintype "passive"))
      (node (ref "CN11") (pin "22") (pinfunction "22_22") (pintype "passive"))
      (node (ref "CN11") (pin "49") (pinfunction "49_49") (pintype "passive"))
      (node (ref "CN11") (pin "60") (pinfunction "60_60") (pintype "passive"))
      (node (ref "CN11") (pin "8") (pinfunction "8_8") (pintype "passive"))
      (node (ref "CN12") (pin "20") (pinfunction "20_20") (pintype "passive"))
      (node (ref "CN12") (pin "39") (pinfunction "39_39") (pintype "passive"))
      (node (ref "CN12") (pin "54") (pinfunction "54_54") (pintype "passive"))
      (node (ref "CN12") (pin "63") (pinfunction "63_63") (pintype "passive"))
      (node (ref "CN12") (pin "9") (pinfunction "9_9") (pintype "passive"))
      (node (ref "CN15") (pin "1") (pinfunction "COMMON_1") (pintype "passive"))
      (node (ref "CN15") (pin "2") (pinfunction "NO_2") (pintype "passive"))
      (node (ref "CN16") (pin "1") (pinfunction "COMMON_1") (pintype "passive"))
      (node (ref "CN16") (pin "2") (pinfunction "NO_2") (pintype "passive"))
      (node (ref "CN7") (pin "8") (pinfunction "8_8") (pintype "passive"))
      (node (ref "CN8") (pin "11") (pinfunction "11_11") (pintype "passive"))
      (node (ref "CN8") (pin "13") (pinfunction "13_13") (pintype "passive"))
      (node (ref "CN9") (pin "12") (pinfunction "12_12") (pintype "passive"))
      (node (ref "CN9") (pin "23") (pinfunction "23_23") (pintype "passive"))
      (node (ref "Q1") (pin "2") (pinfunction "E_2") (pintype "passive"))
      (node (ref "Q2") (pin "2") (pinfunction "E_2") (pintype "passive"))
      (node (ref "Q3") (pin "2") (pinfunction "E_2") (pintype "passive"))
      (node (ref "R68") (pin "1") (pinfunction "1_1") (pintype "passive"))
      (node (ref "R69") (pin "1") (pinfunction "1_1") (pintype "passive"))
      (node (ref "R70") (pin "1") (pinfunction "1_1") (pintype "passive"))
    )
    (net (code "135") (name "IOREF") (class "Default")
      (node (ref "CN11") (pin "12") (pinfunction "12_12") (pintype "passive"))
      (node (ref "CN8") (pin "3") (pinfunction "3_3") (pintype "passive"))
      (node (ref "SB10") (pin "2") (pinfunction "2_2") (pintype "passive"))
      (node (ref "SB11") (pin "2") (pinfunction "2_2") (pintype "passive"))
      (node (ref "SB20") (pin "2") (pinfunction "2_2") (pintype "passive"))
    )
    (net (code "136") (name "Net-(CN7-Pad5)") (class "Default")
      (node (ref "CN7") (pin "5") (pinfunction "5_5") (pintype "passive"))
      (node (ref "SB7") (pin "2") (pinfunction "2_2") (pintype "passive"))
    )
    (net (code "137") (name "Net-(CN7-Pad14)") (class "Default")
      (node (ref "CN7") (pin "14") (pinfunction "14_14") (pintype "passive"))
      (node (ref "SB33") (pin "1") (pinfunction "1_1") (pintype "passive"))
      (node (ref "SB35") (pin "1") (pinfunction "1_1") (pintype "passive"))
    )
    (net (code "138") (name "Net-(CN7-Pad15)") (class "Default")
      (node (ref "CN7") (pin "15") (pinfunction "15_15") (pintype "passive"))
      (node (ref "SB26") (pin "2") (pinfunction "2_2") (pintype "passive"))
    )
    (net (code "139") (name "Net-(CN9-Pad9)") (class "Default")
      (node (ref "CN9") (pin "9") (pinfunction "9_9") (pintype "passive"))
      (node (ref "SB53") (pin "2") (pinfunction "2_2") (pintype "passive"))
      (node (ref "SB55") (pin "2") (pinfunction "2_2") (pintype "passive"))
    )
    (net (code "140") (name "Net-(CN9-Pad11)") (class "Default")
      (node (ref "CN9") (pin "11") (pinfunction "11_11") (pintype "passive"))
      (node (ref "SB60") (pin "2") (pinfunction "2_2") (pintype "passive"))
      (node (ref "SB62") (pin "2") (pinfunction "2_2") (pintype "passive"))
      (node (ref "SB65") (pin "2") (pinfunction "2_2") (pintype "passive"))
    )
    (net (code "141") (name "Net-(CN9-Pad13)") (class "Default")
      (node (ref "CN9") (pin "13") (pinfunction "13_13") (pintype "passive"))
      (node (ref "SB69") (pin "2") (pinfunction "2_2") (pintype "passive"))
    )
    (net (code "142") (name "Net-(CN9-Pad14)") (class "Default")
      (node (ref "CN9") (pin "14") (pinfunction "14_14") (pintype "passive"))
      (node (ref "SB67") (pin "1") (pinfunction "1_1") (pintype "passive"))
    )
    (net (code "143") (name "Net-(CN9-Pad15)") (class "Default")
      (node (ref "CN9") (pin "15") (pinfunction "15_15") (pintype "passive"))
      (node (ref "SB70") (pin "2") (pinfunction "2_2") (pintype "passive"))
    )
    (net (code "144") (name "Net-(CN9-Pad20)") (class "Default")
      (node (ref "CN9") (pin "20") (pinfunction "20_20") (pintype "passive"))
      (node (ref "SB71") (pin "1") (pinfunction "1_1") (pintype "passive"))
    )
    (net (code "145") (name "Net-(CN10-Pad4)") (class "Default")
      (node (ref "CN10") (pin "4") (pinfunction "4_4") (pintype "passive"))
      (node (ref "SB28") (pin "1") (pinfunction "1_1") (pintype "passive"))
    )
    (net (code "146") (name "Net-(CN10-Pad7)") (class "Default")
      (node (ref "CN10") (pin "7") (pinfunction "7_7") (pintype "passive"))
      (node (ref "SB37") (pin "2") (pinfunction "2_2") (pintype "passive"))
      (node (ref "SB38") (pin "2") (pinfunction "2_2") (pintype "passive"))
    )
    (net (code "147") (name "Net-(CN10-Pad9)") (class "Default")
      (node (ref "CN10") (pin "9") (pinfunction "9_9") (pintype "passive"))
      (node (ref "SB48") (pin "2") (pinfunction "2_2") (pintype "passive"))
      (node (ref "SB49") (pin "2") (pinfunction "2_2") (pintype "passive"))
    )
    (net (code "148") (name "Net-(CN10-Pad11)") (class "Default")
      (node (ref "CN10") (pin "11") (pinfunction "11_11") (pintype "passive"))
      (node (ref "SB50") (pin "2") (pinfunction "2_2") (pintype "passive"))
      (node (ref "SB54") (pin "2") (pinfunction "2_2") (pintype "passive"))
    )
    (net (code "149") (name "Net-(CN10-Pad13)") (class "Default")
      (node (ref "CN10") (pin "13") (pinfunction "13_13") (pintype "passive"))
      (node (ref "SB59") (pin "2") (pinfunction "2_2") (pintype "passive"))
      (node (ref "SB61") (pin "2") (pinfunction "2_2") (pintype "passive"))
    )
    (net (code "150") (name "Net-(CN10-Pad15)") (class "Default")
      (node (ref "CN10") (pin "15") (pinfunction "15_15") (pintype "passive"))
      (node (ref "SB63") (pin "2") (pinfunction "2_2") (pintype "passive"))
    )
    (net (code "151") (name "Net-(CN10-Pad28)") (class "Default")
      (node (ref "CN10") (pin "28") (pinfunction "28_28") (pintype "passive"))
      (node (ref "SB73") (pin "1") (pinfunction "1_1") (pintype "passive"))
    )
    (net (code "152") (name "Net-(CN10-Pad29)") (class "Default")
      (node (ref "CN10") (pin "29") (pinfunction "29_29") (pintype "passive"))
      (node (ref "SB75") (pin "2") (pinfunction "2_2") (pintype "passive"))
    )
    (net (code "153") (name "Net-(CN11-Pad69)") (class "Default")
      (node (ref "CN11") (pin "69") (pinfunction "69_69") (pintype "passive"))
      (node (ref "SB81") (pin "2") (pinfunction "2_2") (pintype "passive"))
    )
    (net (code "154") (name "Net-(CN12-Pad1)") (class "Default")
      (node (ref "CN12") (pin "1") (pinfunction "1_1") (pintype "passive"))
      (node (ref "SB15") (pin "2") (pinfunction "2_2") (pintype "passive"))
    )
    (net (code "155") (name "Net-(CN12-Pad2)") (class "Default")
      (node (ref "CN12") (pin "2") (pinfunction "2_2") (pintype "passive"))
      (node (ref "SB14") (pin "1") (pinfunction "1_1") (pintype "passive"))
    )
    (net (code "156") (name "Net-(CN12-Pad7)") (class "Default")
      (node (ref "CN12") (pin "7") (pinfunction "7_7") (pintype "passive"))
      (node (ref "CN7") (pin "6") (pinfunction "6_6") (pintype "passive"))
      (node (ref "SB42") (pin "1") (pinfunction "1_1") (pintype "passive"))
    )
    (net (code "157") (name "Net-(CN12-Pad10)") (class "Default")
      (node (ref "CN12") (pin "10") (pinfunction "10_10") (pintype "passive"))
      (node (ref "SB82") (pin "1") (pinfunction "1_1") (pintype "passive"))
    )
    (net (code "158") (name "Net-(CN12-Pad12)") (class "Default")
      (node (ref "CN12") (pin "12") (pinfunction "12_12") (pintype "passive"))
      (node (ref "SB17") (pin "1") (pinfunction "1_1") (pintype "passive"))
    )
    (net (code "159") (name "Net-(CN12-Pad14)") (class "Default")
      (node (ref "CN12") (pin "14") (pinfunction "14_14") (pintype "passive"))
      (node (ref "SB16") (pin "1") (pinfunction "1_1") (pintype "passive"))
    )
    (net (code "160") (name "Net-(LD1-Pad1)") (class "Default")
      (node (ref "LD1") (pin "1") (pintype "passive"))
      (node (ref "R26") (pin "1") (pinfunction "1_1") (pintype "passive"))
    )
    (net (code "161") (name "Net-(LD2-Pad1)") (class "Default")
      (node (ref "LD2") (pin "1") (pintype "passive"))
      (node (ref "R28") (pin "1") (pinfunction "1_1") (pintype "passive"))
    )
    (net (code "162") (name "Net-(LD3-Pad1)") (class "Default")
      (node (ref "LD3") (pin "1") (pintype "passive"))
      (node (ref "R27") (pin "1") (pinfunction "1_1") (pintype "passive"))
    )
    (net (code "163") (name "Net-(Q1-B)") (class "Default")
      (node (ref "Q1") (pin "1") (pinfunction "B_1") (pintype "passive"))
      (node (ref "R68") (pin "2") (pinfunction "2_2") (pintype "passive"))
      (node (ref "R73") (pin "2") (pinfunction "2_2") (pintype "passive"))
    )
    (net (code "164") (name "Net-(Q1-C)") (class "Default")
      (node (ref "LD1") (pin "2") (pintype "passive"))
      (node (ref "Q1") (pin "3") (pinfunction "C_3") (pintype "passive"))
    )
    (net (code "165") (name "Net-(Q2-B)") (class "Default")
      (node (ref "Q2") (pin "1") (pinfunction "B_1") (pintype "passive"))
      (node (ref "R69") (pin "2") (pinfunction "2_2") (pintype "passive"))
      (node (ref "R71") (pin "2") (pinfunction "2_2") (pintype "passive"))
    )
    (net (code "166") (name "Net-(Q2-C)") (class "Default")
      (node (ref "LD2") (pin "2") (pintype "passive"))
      (node (ref "Q2") (pin "3") (pinfunction "C_3") (pintype "passive"))
    )
    (net (code "167") (name "Net-(Q3-B)") (class "Default")
      (node (ref "Q3") (pin "1") (pinfunction "B_1") (pintype "passive"))
      (node (ref "R70") (pin "2") (pinfunction "2_2") (pintype "passive"))
      (node (ref "R72") (pin "2") (pinfunction "2_2") (pintype "passive"))
    )
    (net (code "168") (name "Net-(Q3-C)") (class "Default")
      (node (ref "LD3") (pin "2") (pintype "passive"))
      (node (ref "Q3") (pin "3") (pinfunction "C_3") (pintype "passive"))
    )
    (net (code "169") (name "Net-(R73-Pad1)") (class "Default")
      (node (ref "R73") (pin "1") (pinfunction "1_1") (pintype "passive"))
      (node (ref "SB39") (pin "2") (pinfunction "2_2") (pintype "passive"))
      (node (ref "SB47") (pin "2") (pinfunction "2_2") (pintype "passive"))
    )
    (net (code "170") (name "VBAT") (class "Default")
      (node (ref "CN11") (pin "33") (pinfunction "33_33") (pintype "passive"))
    )
    (net (code "171") (name "VDDA") (class "Default")
      (node (ref "CN10") (pin "1") (pinfunction "1_1") (pintype "passive"))
    )
    (net (code "172") (name "VDD_MCU") (class "Default")
      (node (ref "SB11") (pin "1") (pinfunction "1_1") (pintype "passive"))
    )
    (net (code "173") (name "VIN") (class "Default")
      (node (ref "CN11") (pin "24") (pinfunction "24_24") (pintype "passive"))
      (node (ref "CN8") (pin "15") (pinfunction "15_15") (pintype "passive"))
    )
    (net (code "174") (name "VREFP") (class "Default")
      (node (ref "C65") (pin "2") (pinfunction "2_2") (pintype "passive"))
      (node (ref "SB42") (pin "2") (pinfunction "2_2") (pintype "passive"))
    )
    (net (code "175") (name "unconnected-(CN8-Pad1)") (class "Default")
      (node (ref "CN8") (pin "1") (pinfunction "1_1") (pintype "passive+no_connect"))
    )
    (net (code "176") (name "unconnected-(CN11-Pad10)") (class "Default")
      (node (ref "CN11") (pin "10") (pinfunction "10_10") (pintype "passive+no_connect"))
    )
    (net (code "177") (name "unconnected-(CN11-Pad26)") (class "Default")
      (node (ref "CN11") (pin "26") (pinfunction "26_26") (pintype "passive+no_connect"))
    )
    (net (code "178") (name "unconnected-(CN11-Pad67)") (class "Default")
      (node (ref "CN11") (pin "67") (pinfunction "67_67") (pintype "passive+no_connect"))
    )
  )
)
